# uv_brick.net
KiCad netlist of a schematic drawn in EAGLE
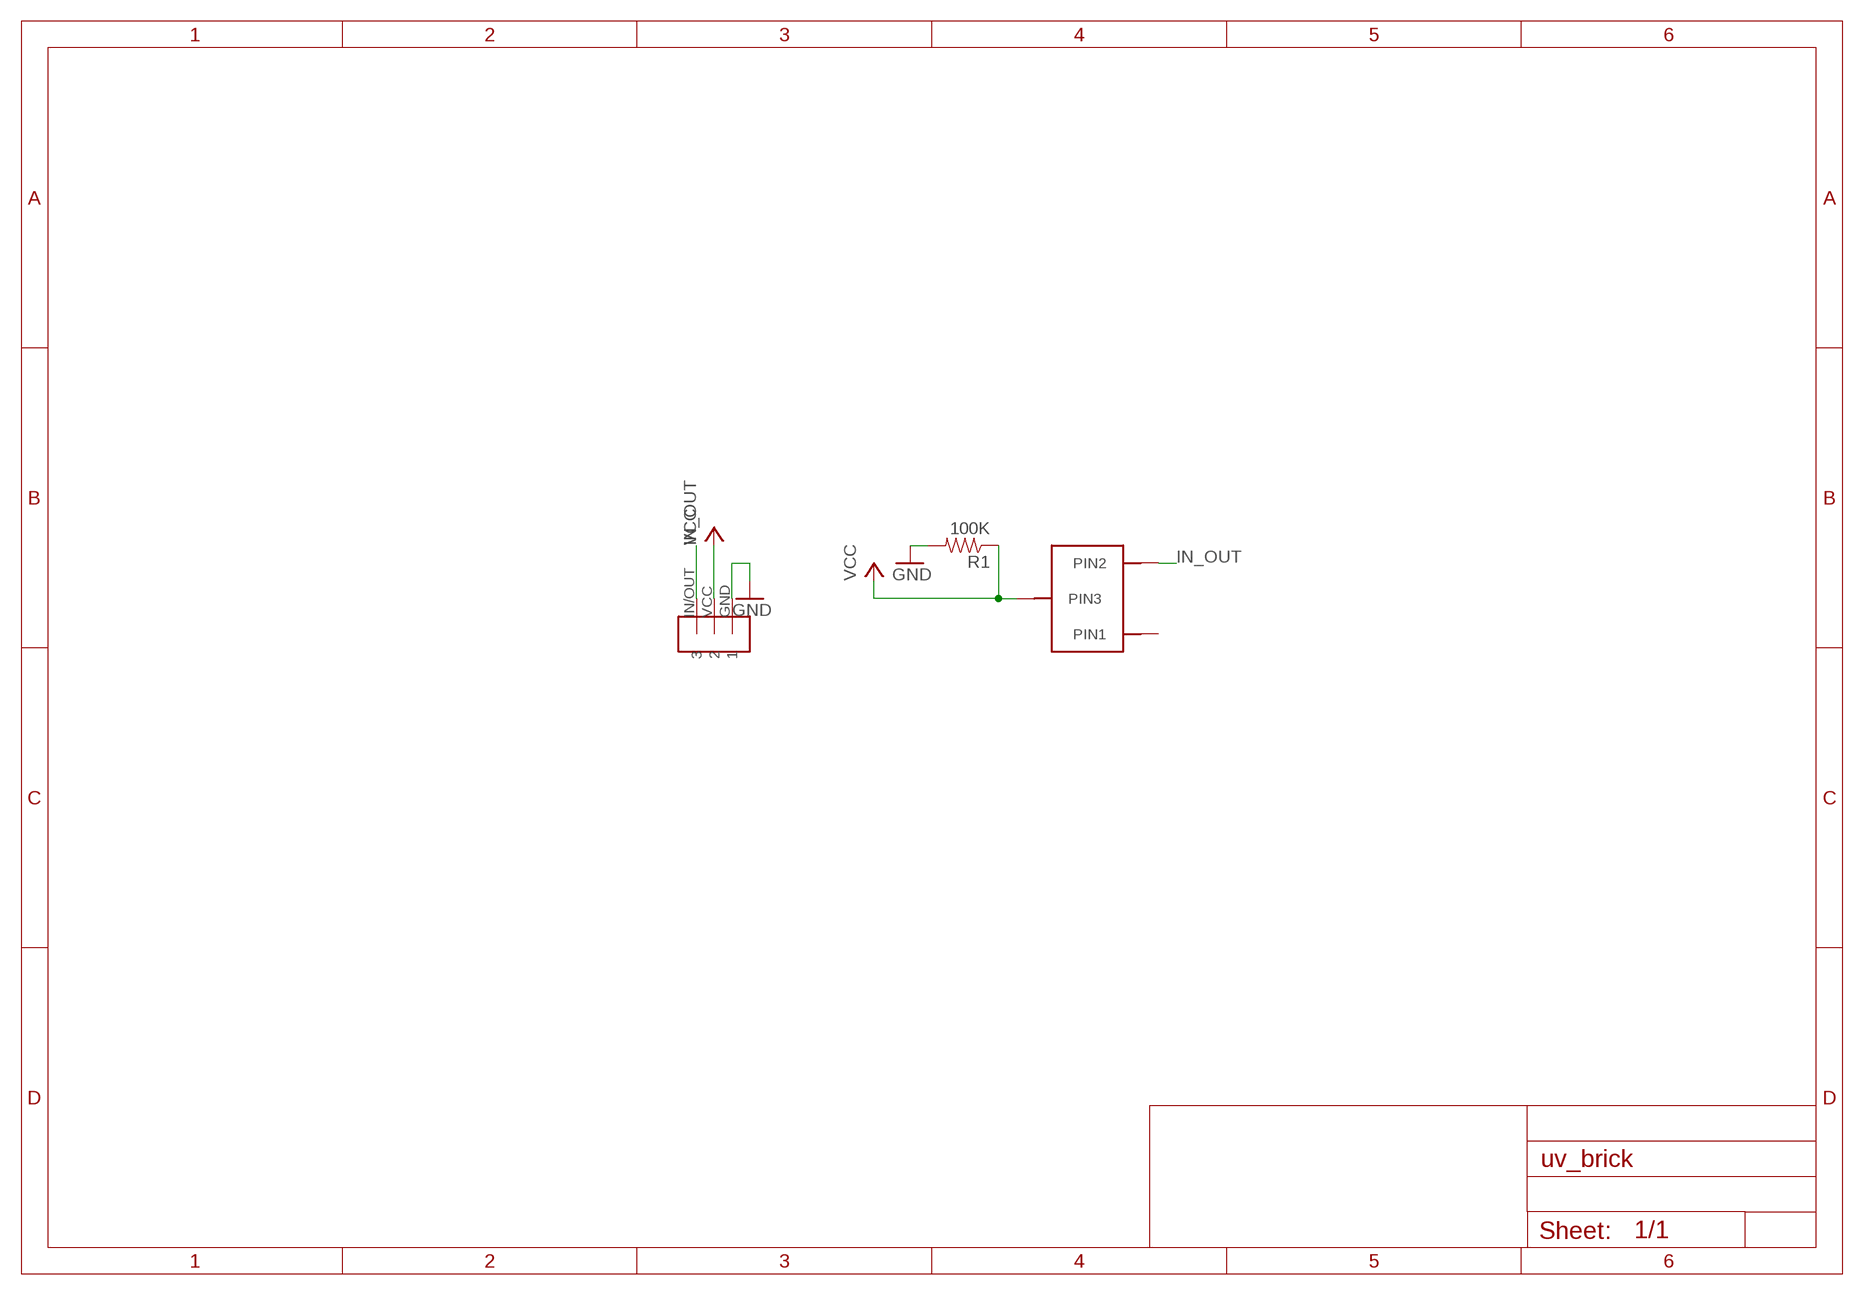
[diagram p0: schematic, sheet 1]

(export (version "E")
  (design (tool "Eeschema 10.0.6"))
  (components
    (comp (ref "R1")
      (value "100K")
      (footprint "eagle-import:0603-RES")
      (libsource (lib "eagle-import") (part "RESISTOR0603-RES"))
    )
    (comp (ref "U$1")
      (value "GAASP-G6262")
      (footprint "eagle-import:GAASP-G6262")
      (libsource (lib "eagle-import") (part "GAASP-G6262"))
    )
    (comp (ref "U$2")
      (value "BRICK-3PIN")
      (footprint "eagle-import:BRICK_3PIN")
      (libsource (lib "eagle-import") (part "BRICK-3PIN"))
    )
  )
  (nets
    (net (code "1") (name "/IN_OUT") (class "Default")
      (node (ref "U$1") (pin "2") (pinfunction "PIN2_2") (pintype "bidirectional"))
      (node (ref "U$2") (pin "IN/OUT") (pinfunction "3_IN/OUT") (pintype "bidirectional"))
    )
    (net (code "2") (name "GND") (class "Default")
      (node (ref "R1") (pin "2") (pinfunction "2_2") (pintype "passive"))
      (node (ref "U$2") (pin "GND") (pinfunction "1_GND") (pintype "bidirectional"))
    )
    (net (code "3") (name "VCC") (class "Default")
      (node (ref "R1") (pin "1") (pinfunction "1_1") (pintype "passive"))
      (node (ref "U$1") (pin "3") (pinfunction "PIN3_3") (pintype "bidirectional"))
      (node (ref "U$2") (pin "VCC") (pinfunction "2_VCC") (pintype "bidirectional"))
    )
    (net (code "4") (name "unconnected-(U$1-PIN1-Pad1)") (class "Default")
      (node (ref "U$1") (pin "1") (pinfunction "PIN1_1") (pintype "bidirectional"))
    )
  )
)
